# LPCB220_-_MLP_INTERFACE.net
KiCad netlist of a schematic drawn in Altium Designer
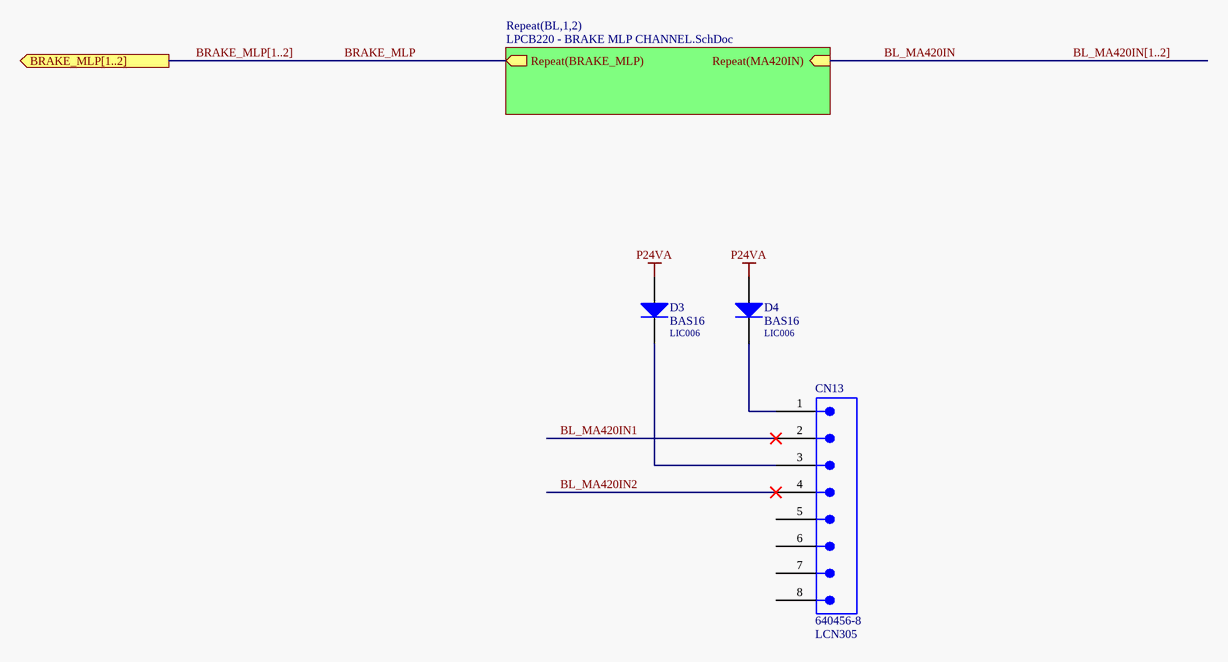
[diagram p0: LPCB220 - MLP INTERFACE.SchDoc]

(export (version "E")
  (design (tool "Eeschema 10.0.6"))
  (components
    (comp (ref "CN13")
      (value "640456-8")
      (footprint "640456-8")
      (description "Connector, Male Header, 8 Way")
      (fields (field (name "LDL_NUMBER") "LCN305"))
      (libsource (lib "LDL_Connectors") (part "640456-8"))
    )
    (comp (ref "D3")
      (value "BAS16")
      (footprint "LFP021__SOT23")
      (description "Diode, Small Signal, 0.2A, 85V, SMD SOT-23 [LIC006]")
      (fields (field (name "LDL_NUMBER") "LIC006"))
      (libsource (lib "LDL_Semiconductors") (part "BAS16"))
    )
    (comp (ref "D4")
      (value "BAS16")
      (footprint "LFP021__SOT23")
      (description "Diode, Small Signal, 0.2A, 85V, SMD SOT-23 [LIC006]")
      (fields (field (name "LDL_NUMBER") "LIC006"))
      (libsource (lib "LDL_Semiconductors") (part "BAS16"))
    )
  )
  (nets
    (net (code "4") (name "/BL_MA420IN1") (class "Default")
      (node (ref "CN13") (pin "2") (pinfunction "2_2") (pintype "passive+no_connect"))
    )
    (net (code "5") (name "/BL_MA420IN2") (class "Default")
      (node (ref "CN13") (pin "4") (pinfunction "4_4") (pintype "passive+no_connect"))
    )
    (net (code "9") (name "Net-(D3-K)") (class "Default")
      (node (ref "CN13") (pin "3") (pinfunction "3_3") (pintype "passive"))
      (node (ref "D3") (pin "3") (pinfunction "K_3") (pintype "passive"))
    )
    (net (code "10") (name "Net-(D4-K)") (class "Default")
      (node (ref "CN13") (pin "1") (pinfunction "1_1") (pintype "passive"))
      (node (ref "D4") (pin "3") (pinfunction "K_3") (pintype "passive"))
    )
    (net (code "11") (name "P24VA") (class "Default")
      (node (ref "D3") (pin "1") (pinfunction "A_1") (pintype "passive"))
      (node (ref "D4") (pin "1") (pinfunction "A_1") (pintype "passive"))
    )
    (net (code "12") (name "unconnected-(CN13-Pad5)") (class "Default")
      (node (ref "CN13") (pin "5") (pinfunction "5_5") (pintype "passive"))
    )
    (net (code "13") (name "unconnected-(CN13-Pad6)") (class "Default")
      (node (ref "CN13") (pin "6") (pinfunction "6_6") (pintype "passive"))
    )
    (net (code "14") (name "unconnected-(CN13-Pad7)") (class "Default")
      (node (ref "CN13") (pin "7") (pinfunction "7_7") (pintype "passive"))
    )
    (net (code "15") (name "unconnected-(CN13-Pad8)") (class "Default")
      (node (ref "CN13") (pin "8") (pinfunction "8_8") (pintype "passive"))
    )
  )
)
